# OTP4.net
KiCad netlist of a schematic drawn in Altium Designer
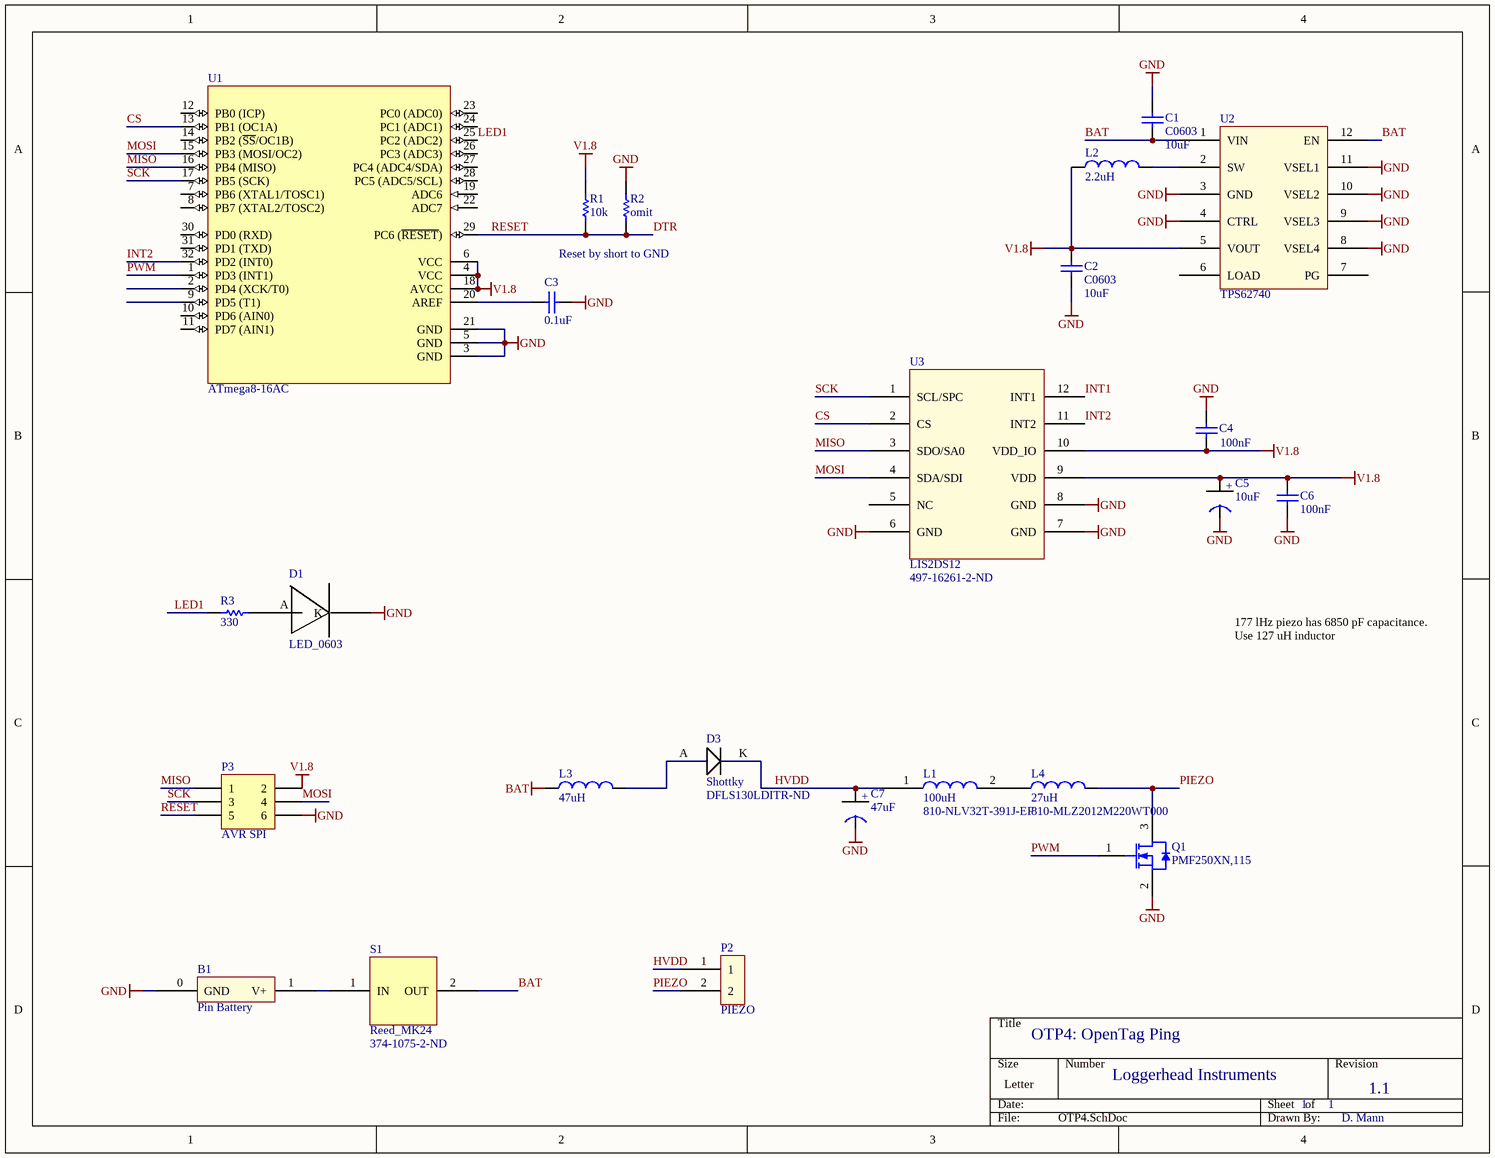
[diagram p0: OTP4.SchDoc]

(export (version "E")
  (design (tool "Eeschema 10.0.6"))
  (components
    (comp (ref "B1")
      (value "Pin Battery")
      (footprint "Battery_Pin")
      (libsource (lib "Loggerhead") (part "Battery_Pin"))
    )
    (comp (ref "C1")
      (value "C0603")
      (footprint "0603")
      (description "Ceramic Chip Capacitor - Standard")
      (fields (field (name "ALTIUM_VALUE") "10uF") (field (name "PUBLISHER") "Altium Limited"))
      (libsource (lib "KEMET Chip Capacitor") (part "C0603"))
    )
    (comp (ref "C2")
      (value "C0603")
      (footprint "0603")
      (description "Ceramic Chip Capacitor - Standard")
      (fields (field (name "ALTIUM_VALUE") "10uF") (field (name "PUBLISHER") "Altium Limited"))
      (libsource (lib "KEMET Chip Capacitor") (part "C0603"))
    )
    (comp (ref "C3")
      (value "0.1uF")
      (footprint "0402")
      (description "Ceramic Chip Capacitor - Standard")
      (fields (field (name "PUBLISHER") "Altium Limited"))
      (libsource (lib "KEMET Chip Capacitor") (part "C0402"))
    )
    (comp (ref "C4")
      (value "100nF")
      (footprint "0402")
      (description "Ceramic Chip Capacitor - Standard")
      (fields (field (name "PUBLISHER") "Altium Limited"))
      (libsource (lib "KEMET Chip Capacitor") (part "C0402"))
    )
    (comp (ref "C5") (value "10uF") (footprint "Tant0805") (libsource (lib "Loggerhead") (part "Tant0805")))
    (comp (ref "C6")
      (value "100nF")
      (footprint "0402")
      (description "Ceramic Chip Capacitor - Standard")
      (fields (field (name "PUBLISHER") "Altium Limited"))
      (libsource (lib "KEMET Chip Capacitor") (part "C0402"))
    )
    (comp (ref "C7") (value "47uF") (footprint "Tant0805") (libsource (lib "Loggerhead") (part "Tant0805")))
    (comp (ref "D1")
      (value "LED_0603")
      (footprint "Diode0603")
      (libsource (lib "Loggerhead") (part "LED_0603"))
    )
    (comp (ref "D3")
      (value "Shottky")
      (footprint "DFLS130")
      (fields (field (name "SUPPLIER PART NUMBER 1") "DFLS130LDITR-ND"))
      (libsource (lib "Loggerhead") (part "DFLS130"))
    )
    (comp (ref "L1")
      (value "100uH")
      (footprint "Inductor_NLV32T")
      (fields (field (name "SUPPLIER PART NUMBER 1") "810-NLV32T-391J-EF"))
      (libsource (lib "Loggerhead") (part "Inductor_NLV32T"))
    )
    (comp (ref "L2")
      (value "2.2uH")
      (footprint "Inductor KLZ1608AHR")
      (libsource (lib "Loggerhead") (part "Inductor KLZ1608"))
    )
    (comp (ref "L3")
      (value "47uH")
      (footprint "Inductor KLZ1608AHR")
      (libsource (lib "Loggerhead") (part "Inductor KLZ1608"))
    )
    (comp (ref "L4")
      (value "27uH")
      (footprint "Inductor MLZ2012M220WT000")
      (fields (field (name "SUPPLIER PART NUMBER 1") "810-MLZ2012M220WT000"))
      (libsource (lib "Loggerhead") (part "Inductor MLZ2012M220WT000"))
    )
    (comp (ref "P2") (value "PIEZO") (footprint "PIEZO") (libsource (lib "Loggerhead") (part "PIEZO")))
    (comp (ref "P3")
      (value "AVR SPI")
      (footprint "HDR2X3")
      (description "Header, 3-Pin, Dual row")
      (fields (field (name "PUBLISHER") "Altium Limited"))
      (libsource (lib "Miscellaneous Connectors") (part "Header 3X2"))
    )
    (comp (ref "Q1")
      (value "PMF250XN,115")
      (footprint "NXP-SOT323_N")
      (description "N-Channel Trench MOSFET, 30 V, 0.9 A, -55 to 150 degC, 3-Pin SOT323, Tape and Reel")
      (fields (field (name "MANUFACTURER") "NXP Semiconductors"))
      (libsource (lib "NXP Semiconductors Standard MOSFETs") (part "PMF250XN,115"))
    )
    (comp (ref "R1")
      (value "10k")
      (footprint "3-0603")
      (fields (field (name "PUBLISHER") "Altium Limited"))
      (libsource (lib "Panasonic Resistor") (part "ERJ3RK"))
    )
    (comp (ref "R2")
      (value "omit")
      (footprint "3-0603")
      (fields (field (name "PUBLISHER") "Altium Limited"))
      (libsource (lib "Panasonic Resistor") (part "ERJ3RK"))
    )
    (comp (ref "R3")
      (value "330")
      (footprint "3-0603")
      (fields (field (name "PUBLISHER") "Altium Limited"))
      (libsource (lib "Panasonic Resistor") (part "ERJ3RK"))
    )
    (comp (ref "S1")
      (value "Reed_MK24")
      (footprint "Reed MK24-B-3")
      (fields (field (name "SUPPLIER PART NUMBER 1") "374-1075-2-ND"))
      (libsource (lib "Loggerhead") (part "Reed_MK24"))
    )
    (comp (ref "U1")
      (value "ATmega8-16AC")
      (footprint "32M1-A_M")
      (description "8-Bit AVR Microcontroller with 8K Bytes of In-System Programmable Flash Memory")
      (fields (field (name "PUBLISHER") "Altium Limited"))
      (libsource (lib "Atmel Microcontroller 8-Bit AVR") (part "ATmega8-16AC"))
    )
    (comp (ref "U2")
      (value "TPS62740")
      (footprint "TPS6274x")
      (libsource (lib "Loggerhead") (part "TPS6274x"))
    )
    (comp (ref "U3")
      (value "LIS2DS12")
      (footprint "LGA-12")
      (fields (field (name "SUPPLIER PART NUMBER 1") "497-16261-2-ND"))
      (libsource (lib "Loggerhead") (part "LIS2DS12"))
    )
  )
  (nets
    (net (code "1") (name "/CS") (class "Default")
      (node (ref "U1") (pin "13") (pinfunction "PB1_(OC1A)_13") (pintype "bidirectional"))
      (node (ref "U3") (pin "2") (pinfunction "CS_2") (pintype "passive"))
    )
    (net (code "2") (name "/DTR") (class "Default")
      (node (ref "P3") (pin "5") (pinfunction "5_5") (pintype "passive"))
      (node (ref "R1") (pin "1") (pinfunction "1_1") (pintype "passive"))
      (node (ref "R2") (pin "1") (pinfunction "1_1") (pintype "passive"))
      (node (ref "U1") (pin "29") (pinfunction "PC6_(~{RESET})_29") (pintype "bidirectional"))
    )
    (net (code "3") (name "/HVDD") (class "Default")
      (node (ref "C7") (pin "2") (pinfunction "+_2") (pintype "passive"))
      (node (ref "D3") (pin "K") (pintype "passive"))
      (node (ref "L1") (pin "1") (pinfunction "1_1") (pintype "passive"))
      (node (ref "P2") (pin "1") (pinfunction "1_1") (pintype "passive"))
    )
    (net (code "4") (name "/INT1") (class "Default")
      (node (ref "U3") (pin "12") (pinfunction "INT1_12") (pintype "passive"))
    )
    (net (code "5") (name "/INT2") (class "Default")
      (node (ref "U1") (pin "32") (pinfunction "PD2_(INT0)_32") (pintype "bidirectional"))
      (node (ref "U3") (pin "11") (pinfunction "INT2_11") (pintype "passive"))
    )
    (net (code "6") (name "/LED1") (class "Default")
      (node (ref "R3") (pin "1") (pinfunction "1_1") (pintype "passive"))
      (node (ref "U1") (pin "25") (pinfunction "PC2_(ADC2)_25") (pintype "bidirectional"))
    )
    (net (code "7") (name "/MISO") (class "Default")
      (node (ref "P3") (pin "1") (pinfunction "1_1") (pintype "passive"))
      (node (ref "U1") (pin "16") (pinfunction "PB4_(MISO)_16") (pintype "bidirectional"))
      (node (ref "U3") (pin "3") (pinfunction "SDO/SA0_3") (pintype "passive"))
    )
    (net (code "8") (name "/MOSI") (class "Default")
      (node (ref "P3") (pin "4") (pinfunction "4_4") (pintype "passive"))
      (node (ref "U1") (pin "15") (pinfunction "PB3_(MOSI/OC2)_15") (pintype "bidirectional"))
      (node (ref "U3") (pin "4") (pinfunction "SDA/SDI_4") (pintype "passive"))
    )
    (net (code "9") (name "/PIEZO") (class "Default")
      (node (ref "L4") (pin "2") (pinfunction "2_2") (pintype "passive"))
      (node (ref "P2") (pin "2") (pinfunction "2_2") (pintype "passive"))
      (node (ref "Q1") (pin "3") (pinfunction "D_3") (pintype "passive"))
    )
    (net (code "10") (name "/PWM") (class "Default")
      (node (ref "Q1") (pin "1") (pinfunction "G_1") (pintype "passive"))
      (node (ref "U1") (pin "1") (pinfunction "PD3_(INT1)_1") (pintype "bidirectional"))
    )
    (net (code "11") (name "/SCK") (class "Default")
      (node (ref "P3") (pin "3") (pinfunction "3_3") (pintype "passive"))
      (node (ref "U1") (pin "17") (pinfunction "PB5_(SCK)_17") (pintype "bidirectional"))
      (node (ref "U3") (pin "1") (pinfunction "SCL/SPC_1") (pintype "passive"))
    )
    (net (code "12") (name "BAT") (class "Default")
      (node (ref "C1") (pin "1") (pinfunction "1_1") (pintype "passive"))
      (node (ref "L3") (pin "1") (pinfunction "1_1") (pintype "passive"))
      (node (ref "S1") (pin "2") (pinfunction "OUT_2") (pintype "passive"))
      (node (ref "U2") (pin "1") (pinfunction "VIN_1") (pintype "passive"))
      (node (ref "U2") (pin "12") (pinfunction "EN_12") (pintype "passive"))
    )
    (net (code "13") (name "GND") (class "Default")
      (node (ref "B1") (pin "0") (pinfunction "GND_0") (pintype "passive"))
      (node (ref "C1") (pin "2") (pinfunction "2_2") (pintype "passive"))
      (node (ref "C2") (pin "1") (pinfunction "1_1") (pintype "passive"))
      (node (ref "C3") (pin "2") (pinfunction "2_2") (pintype "passive"))
      (node (ref "C4") (pin "2") (pinfunction "2_2") (pintype "passive"))
      (node (ref "C5") (pin "1") (pinfunction "GND_1") (pintype "passive"))
      (node (ref "C6") (pin "2") (pinfunction "2_2") (pintype "passive"))
      (node (ref "C7") (pin "1") (pinfunction "GND_1") (pintype "passive"))
      (node (ref "D1") (pin "K") (pinfunction "K_K") (pintype "passive"))
      (node (ref "P3") (pin "6") (pinfunction "6_6") (pintype "passive"))
      (node (ref "Q1") (pin "2") (pinfunction "S_2") (pintype "passive"))
      (node (ref "R2") (pin "2") (pinfunction "2_2") (pintype "passive"))
      (node (ref "U1") (pin "21") (pinfunction "GND_21") (pintype "power_in"))
      (node (ref "U1") (pin "3") (pinfunction "GND_3") (pintype "power_in"))
      (node (ref "U1") (pin "5") (pinfunction "GND_5") (pintype "power_in"))
      (node (ref "U2") (pin "10") (pinfunction "VSEL2_10") (pintype "passive"))
      (node (ref "U2") (pin "11") (pinfunction "VSEL1_11") (pintype "passive"))
      (node (ref "U2") (pin "3") (pinfunction "GND_3") (pintype "passive"))
      (node (ref "U2") (pin "4") (pinfunction "CTRL_4") (pintype "passive"))
      (node (ref "U2") (pin "8") (pinfunction "VSEL4_8") (pintype "passive"))
      (node (ref "U2") (pin "9") (pinfunction "VSEL3_9") (pintype "passive"))
      (node (ref "U3") (pin "6") (pinfunction "GND_6") (pintype "passive"))
      (node (ref "U3") (pin "7") (pinfunction "GND_7") (pintype "passive"))
      (node (ref "U3") (pin "8") (pinfunction "GND_8") (pintype "passive"))
    )
    (net (code "14") (name "Net-(B1-V+)") (class "Default")
      (node (ref "B1") (pin "1") (pinfunction "V+_1") (pintype "passive"))
      (node (ref "S1") (pin "1") (pinfunction "IN_1") (pintype "passive"))
    )
    (net (code "15") (name "Net-(D1-PadA)") (class "Default")
      (node (ref "D1") (pin "A") (pinfunction "A_A") (pintype "passive"))
      (node (ref "R3") (pin "2") (pinfunction "2_2") (pintype "passive"))
    )
    (net (code "16") (name "Net-(D3-PadA)") (class "Default")
      (node (ref "D3") (pin "A") (pintype "passive"))
      (node (ref "L3") (pin "2") (pinfunction "2_2") (pintype "passive"))
    )
    (net (code "17") (name "Net-(L1-Pad2)") (class "Default")
      (node (ref "L1") (pin "2") (pinfunction "2_2") (pintype "passive"))
      (node (ref "L4") (pin "1") (pinfunction "1_1") (pintype "passive"))
    )
    (net (code "18") (name "Net-(U1-AREF)") (class "Default")
      (node (ref "C3") (pin "1") (pinfunction "1_1") (pintype "passive"))
      (node (ref "U1") (pin "20") (pinfunction "AREF_20") (pintype "passive"))
    )
    (net (code "19") (name "Net-(U2-SW)") (class "Default")
      (node (ref "L2") (pin "2") (pinfunction "2_2") (pintype "passive"))
      (node (ref "U2") (pin "2") (pinfunction "SW_2") (pintype "passive"))
    )
    (net (code "20") (name "V1.8") (class "Default")
      (node (ref "C2") (pin "2") (pinfunction "2_2") (pintype "passive"))
      (node (ref "C4") (pin "1") (pinfunction "1_1") (pintype "passive"))
      (node (ref "C5") (pin "2") (pinfunction "+_2") (pintype "passive"))
      (node (ref "C6") (pin "1") (pinfunction "1_1") (pintype "passive"))
      (node (ref "L2") (pin "1") (pinfunction "1_1") (pintype "passive"))
      (node (ref "P3") (pin "2") (pinfunction "2_2") (pintype "passive"))
      (node (ref "R1") (pin "2") (pinfunction "2_2") (pintype "passive"))
      (node (ref "U1") (pin "18") (pinfunction "AVCC_18") (pintype "power_in"))
      (node (ref "U1") (pin "4") (pinfunction "VCC_4") (pintype "power_in"))
      (node (ref "U1") (pin "6") (pinfunction "VCC_6") (pintype "power_in"))
      (node (ref "U2") (pin "5") (pinfunction "VOUT_5") (pintype "passive"))
      (node (ref "U3") (pin "10") (pinfunction "VDD_IO_10") (pintype "passive"))
      (node (ref "U3") (pin "9") (pinfunction "VDD_9") (pintype "passive"))
    )
    (net (code "21") (name "unconnected-(U1-ADC6-Pad19)") (class "Default")
      (node (ref "U1") (pin "19") (pinfunction "ADC6_19") (pintype "input"))
    )
    (net (code "22") (name "unconnected-(U1-ADC7-Pad22)") (class "Default")
      (node (ref "U1") (pin "22") (pinfunction "ADC7_22") (pintype "input"))
    )
    (net (code "23") (name "unconnected-(U1-PB0_(ICP)-Pad12)") (class "Default")
      (node (ref "U1") (pin "12") (pinfunction "PB0_(ICP)_12") (pintype "bidirectional"))
    )
    (net (code "24") (name "unconnected-(U1-PB2_(~{SS}{slash}OC1B)-Pad14)") (class "Default")
      (node (ref "U1") (pin "14") (pinfunction "PB2_(~{SS}/OC1B)_14") (pintype "bidirectional"))
    )
    (net (code "25") (name "unconnected-(U1-PB6_(XTAL1{slash}TOSC1)-Pad7)") (class "Default")
      (node (ref "U1") (pin "7") (pinfunction "PB6_(XTAL1/TOSC1)_7") (pintype "bidirectional"))
    )
    (net (code "26") (name "unconnected-(U1-PB7_(XTAL2{slash}TOSC2)-Pad8)") (class "Default")
      (node (ref "U1") (pin "8") (pinfunction "PB7_(XTAL2/TOSC2)_8") (pintype "bidirectional"))
    )
    (net (code "27") (name "unconnected-(U1-PC0_(ADC0)-Pad23)") (class "Default")
      (node (ref "U1") (pin "23") (pinfunction "PC0_(ADC0)_23") (pintype "bidirectional"))
    )
    (net (code "28") (name "unconnected-(U1-PC1_(ADC1)-Pad24)") (class "Default")
      (node (ref "U1") (pin "24") (pinfunction "PC1_(ADC1)_24") (pintype "bidirectional"))
    )
    (net (code "29") (name "unconnected-(U1-PC3_(ADC3)-Pad26)") (class "Default")
      (node (ref "U1") (pin "26") (pinfunction "PC3_(ADC3)_26") (pintype "bidirectional"))
    )
    (net (code "30") (name "unconnected-(U1-PC4_(ADC4{slash}SDA)-Pad27)") (class "Default")
      (node (ref "U1") (pin "27") (pinfunction "PC4_(ADC4/SDA)_27") (pintype "bidirectional"))
    )
    (net (code "31") (name "unconnected-(U1-PC5_(ADC5{slash}SCL)-Pad28)") (class "Default")
      (node (ref "U1") (pin "28") (pinfunction "PC5_(ADC5/SCL)_28") (pintype "bidirectional"))
    )
    (net (code "32") (name "unconnected-(U1-PD0_(RXD)-Pad30)") (class "Default")
      (node (ref "U1") (pin "30") (pinfunction "PD0_(RXD)_30") (pintype "bidirectional"))
    )
    (net (code "33") (name "unconnected-(U1-PD1_(TXD)-Pad31)") (class "Default")
      (node (ref "U1") (pin "31") (pinfunction "PD1_(TXD)_31") (pintype "bidirectional"))
    )
    (net (code "34") (name "unconnected-(U1-PD4_(XCK{slash}T0)-Pad2)") (class "Default")
      (node (ref "U1") (pin "2") (pinfunction "PD4_(XCK/T0)_2") (pintype "bidirectional"))
    )
    (net (code "35") (name "unconnected-(U1-PD5_(T1)-Pad9)") (class "Default")
      (node (ref "U1") (pin "9") (pinfunction "PD5_(T1)_9") (pintype "bidirectional"))
    )
    (net (code "36") (name "unconnected-(U1-PD6_(AIN0)-Pad10)") (class "Default")
      (node (ref "U1") (pin "10") (pinfunction "PD6_(AIN0)_10") (pintype "bidirectional"))
    )
    (net (code "37") (name "unconnected-(U1-PD7_(AIN1)-Pad11)") (class "Default")
      (node (ref "U1") (pin "11") (pinfunction "PD7_(AIN1)_11") (pintype "bidirectional"))
    )
    (net (code "38") (name "unconnected-(U2-LOAD-Pad6)") (class "Default")
      (node (ref "U2") (pin "6") (pinfunction "LOAD_6") (pintype "passive"))
    )
    (net (code "39") (name "unconnected-(U2-PG-Pad7)") (class "Default")
      (node (ref "U2") (pin "7") (pinfunction "PG_7") (pintype "passive"))
    )
    (net (code "40") (name "unconnected-(U3-NC-Pad5)") (class "Default")
      (node (ref "U3") (pin "5") (pinfunction "NC_5") (pintype "passive"))
    )
  )
)
